# RF.net
KiCad netlist of a schematic drawn in Altium Designer
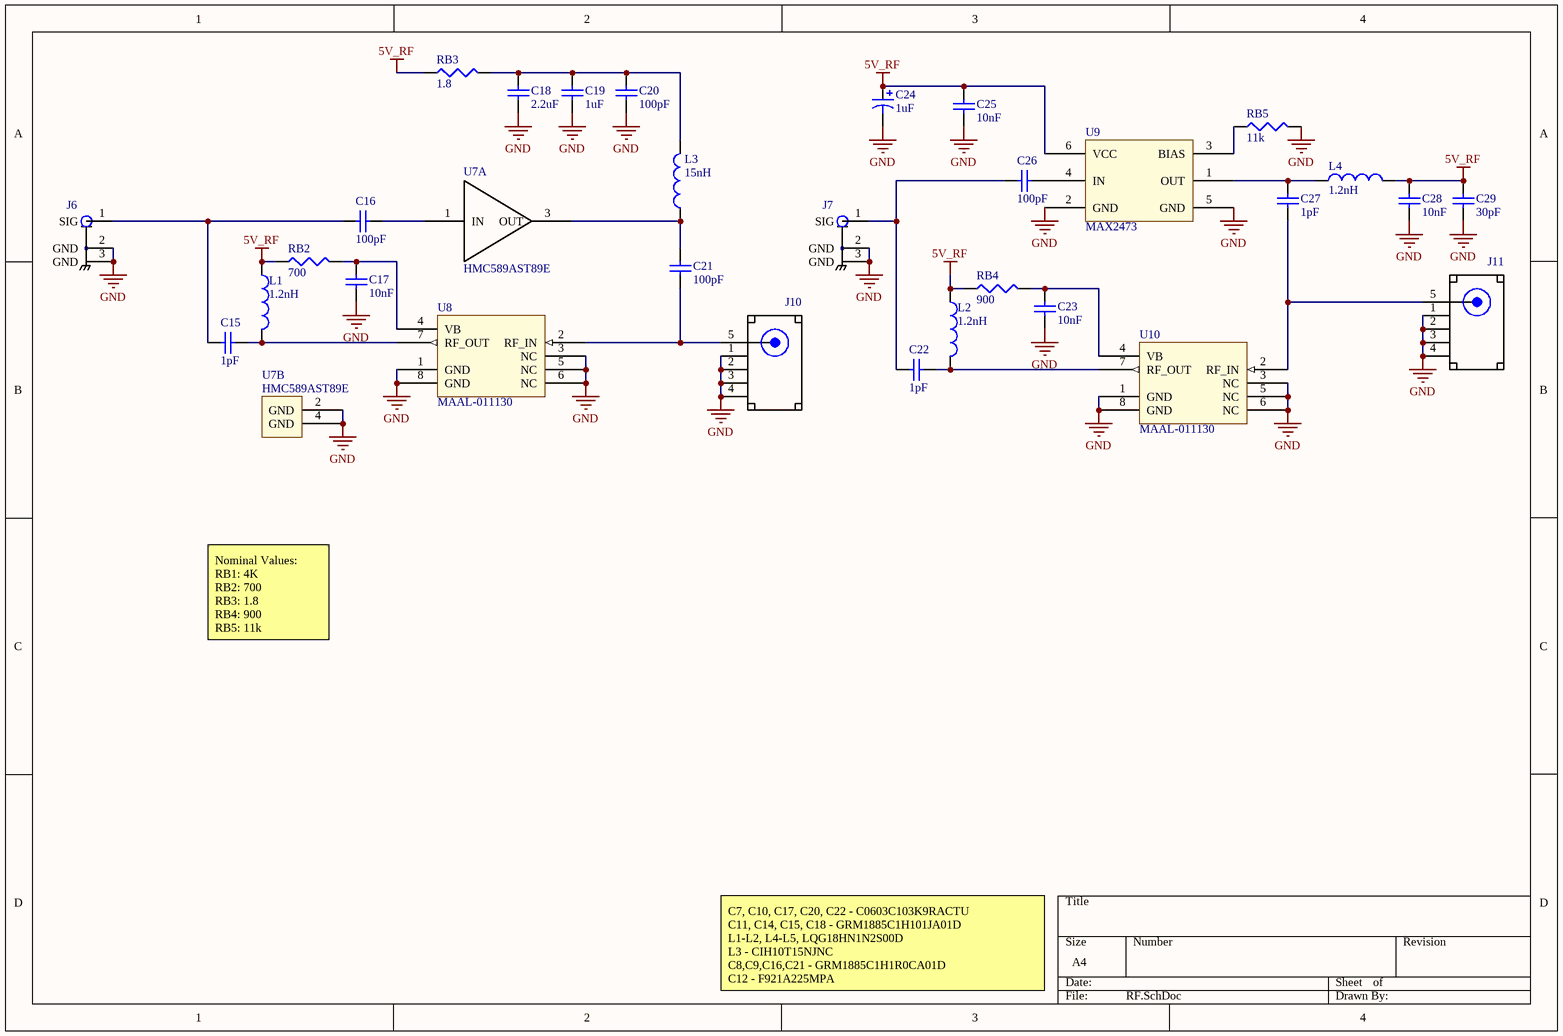
[diagram p0: RF.SchDoc]

(export (version "E")
  (design (tool "Eeschema 10.0.6"))
  (components
    (comp (ref "C15")
      (value "1pF")
      (footprint "CAPC1608X90X35LL10T15")
      (fields (field (name "MANUFACTURER") "Murata") (field (name "PART NUMBER") "GRM1885C1H1R0CA01D"))
      (libsource (lib "Altium Content Vault") (part "CAP"))
    )
    (comp (ref "C16")
      (value "100pF")
      (footprint "CAPC0603(1608)100_N")
      (description "CAP 100pF 50V ±5% 0603 (1608 Metric) Thickness 1mm SMD")
      (fields (field (name "TOLERANCE") "Â±5%"))
      (libsource (lib "Altium Content Vault") (part "CAP"))
    )
    (comp (ref "C17")
      (value "10nF")
      (footprint "CAPC0603(1608)100_L")
      (description "CAP 10nF 6.3V ±10% 0603 (1608 Metric) Thickness 1mm SMD")
      (fields (field (name "TOLERANCE") "Â±10%"))
      (libsource (lib "Altium Content Vault") (part "CAP"))
    )
    (comp (ref "C18")
      (value "2.2uF")
      (footprint "C1206")
      (description "Capacitor (Semiconductor SIM Model)")
      (fields (field (name "MANUFACTURER") "AVX") (field (name "PART NUMBER") "F921A225MPA"))
      (libsource (lib "Miscellaneous Devices") (part "Cap Semi"))
    )
    (comp (ref "C19")
      (value "1uF")
      (footprint "CAPC0603(1608)100_N")
      (description "CAP 100pF 50V ±5% 0603 (1608 Metric) Thickness 1mm SMD")
      (fields (field (name "TOLERANCE") "Â±5%"))
      (libsource (lib "Altium Content Vault") (part "CAP"))
    )
    (comp (ref "C20")
      (value "100pF")
      (footprint "CAPC0603(1608)100_N")
      (description "CAP 100pF 50V ±5% 0603 (1608 Metric) Thickness 1mm SMD")
      (fields (field (name "TOLERANCE") "Â±5%"))
      (libsource (lib "Altium Content Vault") (part "CAP"))
    )
    (comp (ref "C21")
      (value "100pF")
      (footprint "CAPC0603(1608)100_N")
      (description "CAP 100pF 50V ±5% 0603 (1608 Metric) Thickness 1mm SMD")
      (fields (field (name "TOLERANCE") "Â±5%"))
      (libsource (lib "Altium Content Vault") (part "CAP"))
    )
    (comp (ref "C22")
      (value "1pF")
      (footprint "CAPC1608X90X35LL10T15")
      (fields (field (name "MANUFACTURER") "Murata") (field (name "PART NUMBER") "GRM1885C1H1R0CA01D"))
      (libsource (lib "Altium Content Vault") (part "CAP"))
    )
    (comp (ref "C23")
      (value "10nF")
      (footprint "CAPC0603(1608)100_L")
      (description "CAP 10nF 6.3V ±10% 0603 (1608 Metric) Thickness 1mm SMD")
      (fields (field (name "TOLERANCE") "Â±10%"))
      (libsource (lib "Altium Content Vault") (part "CAP"))
    )
    (comp (ref "C24")
      (value "1uF")
      (footprint "CAPAE430X550N")
      (description "Polarized Capacitor (Surface Mount)")
      (fields (field (name "MANUFACTURER") "Panasonic") (field (name "PART NUMBER") "EEE-FC1H1R0R"))
      (libsource (lib "Miscellaneous Devices") (part "Cap Pol3"))
    )
    (comp (ref "C25")
      (value "10nF")
      (footprint "CAPC0603(1608)100_L")
      (description "CAP 10nF 6.3V ±10% 0603 (1608 Metric) Thickness 1mm SMD")
      (fields (field (name "TOLERANCE") "Â±10%"))
      (libsource (lib "Altium Content Vault") (part "CAP"))
    )
    (comp (ref "C26")
      (value "100pF")
      (footprint "CAPC0603(1608)100_N")
      (description "CAP 100pF 50V ±5% 0603 (1608 Metric) Thickness 1mm SMD")
      (fields (field (name "TOLERANCE") "Â±5%"))
      (libsource (lib "Altium Content Vault") (part "CAP"))
    )
    (comp (ref "C27")
      (value "1pF")
      (footprint "CAPC1608X90X35LL10T15")
      (fields (field (name "MANUFACTURER") "Murata") (field (name "PART NUMBER") "GRM1885C1H1R0CA01D"))
      (libsource (lib "Altium Content Vault") (part "CAP"))
    )
    (comp (ref "C28")
      (value "10nF")
      (footprint "CAPC0603(1608)100_L")
      (description "CAP 10nF 6.3V ±10% 0603 (1608 Metric) Thickness 1mm SMD")
      (fields (field (name "TOLERANCE") "Â±10%"))
      (libsource (lib "Altium Content Vault") (part "CAP"))
    )
    (comp (ref "C29")
      (value "30pF")
      (footprint "CAPC1608X90X35LL15T15")
      (fields
        (field (name "MANUFACTURER") "AVX Interconnect / Elco")
        (field (name "PART NUMBER") "06035A300JAT2A")
      )
      (libsource (lib "Altium Content Vault") (part "CAP"))
    )
    (comp (ref "J6")
      (value "1909763-1")
      (footprint "TE_1909763-1")
      (description "CONN UMCC JACK STR 50OHM SMD")
      (fields (field (name "MF") "TE Connectivity"))
      (libsource (lib "Vocore2Parts") (part "1909763-1"))
    )
    (comp (ref "J7")
      (value "1909763-1")
      (footprint "TE_1909763-1")
      (description "CONN UMCC JACK STR 50OHM SMD")
      (fields (field (name "MF") "TE Connectivity"))
      (libsource (lib "Vocore2Parts") (part "1909763-1"))
    )
    (comp (ref "J10")
      (value "5-1814400-1")
      (footprint "CONN_5-1814400-1")
      (description "SMA R/A PCB Skt GZD")
      (fields (field (name "DIGI-KEY_PART_NUMBER") "A97593-ND") (field (name "MF") "TE Connectivity"))
      (libsource (lib "Vocore2Parts") (part "5-1814400-1"))
    )
    (comp (ref "J11")
      (value "5-1814400-1")
      (footprint "CONN_5-1814400-1")
      (description "SMA R/A PCB Skt GZD")
      (fields (field (name "DIGI-KEY_PART_NUMBER") "A97593-ND") (field (name "MF") "TE Connectivity"))
      (libsource (lib "Vocore2Parts") (part "5-1814400-1"))
    )
    (comp (ref "L1")
      (value "1.2nH")
      (footprint "INDC1608L")
      (description "Inductor")
      (fields (field (name "PART NUMBER") "LQG15WH1N2S02D") (field (name "MANUFACTURER") "Murata"))
      (libsource (lib "Miscellaneous Devices") (part "Inductor"))
    )
    (comp (ref "L2")
      (value "1.2nH")
      (footprint "INDC1608L")
      (description "Inductor")
      (fields (field (name "PART NUMBER") "LQG15WH1N2S02D") (field (name "MANUFACTURER") "Murata"))
      (libsource (lib "Miscellaneous Devices") (part "Inductor"))
    )
    (comp (ref "L3")
      (value "15nH")
      (footprint "INDC1608L")
      (description "Inductor")
      (fields (field (name "PART NUMBER") "CIH10T15NJNC") (field (name "MANUFACTURER") "Samsung"))
      (libsource (lib "Miscellaneous Devices") (part "Inductor"))
    )
    (comp (ref "L4")
      (value "1.2nH")
      (footprint "INDC1608L")
      (description "Inductor")
      (fields (field (name "PART NUMBER") "LQG15WH1N2S02D") (field (name "MANUFACTURER") "Murata"))
      (libsource (lib "Miscellaneous Devices") (part "Inductor"))
    )
    (comp (ref "RB2")
      (value "700")
      (footprint "J1-0603")
      (description "Resistor")
      (fields (field (name "PUBLISHER") "Altium Limited"))
      (libsource (lib "Miscellaneous Devices") (part "Res3"))
    )
    (comp (ref "RB3")
      (value "1.8")
      (footprint "J1-0603")
      (description "Resistor")
      (fields (field (name "PUBLISHER") "Altium Limited"))
      (libsource (lib "Miscellaneous Devices") (part "Res3"))
    )
    (comp (ref "RB4")
      (value "900")
      (footprint "C1206")
      (description "Resistor")
      (fields (field (name "PUBLISHER") "Altium Limited"))
      (libsource (lib "Miscellaneous Devices") (part "Res3"))
    )
    (comp (ref "RB5")
      (value "11k")
      (footprint "J1-0603")
      (description "Resistor")
      (fields (field (name "PUBLISHER") "Altium Limited"))
      (libsource (lib "Miscellaneous Devices") (part "Res3"))
    )
    (comp (ref "U7")
      (value "HMC589AST89E")
      (footprint "SOT150P410X160-3N")
      (libsource (lib "Vocore2Parts") (part "HMC589AST89E"))
    )
    (comp (ref "U8")
      (value "MAAL-011130")
      (footprint "PQFN50P200X200X100_HS-9N")
      (libsource (lib "Vocore2Parts") (part "MAAL-011130"))
    )
    (comp (ref "U9")
      (value "MAX2473")
      (footprint "SOT95P280X145-6N")
      (libsource (lib "Vocore2Parts") (part "MAX2473"))
    )
    (comp (ref "U10")
      (value "MAAL-011130")
      (footprint "PQFN50P200X200X100_HS-9N")
      (libsource (lib "Vocore2Parts") (part "MAAL-011130"))
    )
  )
  (nets
    (net (code "1") (name "5V_RF") (class "Default")
      (node (ref "C24") (pin "1") (pinfunction "1_1") (pintype "passive"))
      (node (ref "C25") (pin "2") (pinfunction "2_2") (pintype "passive"))
      (node (ref "C28") (pin "2") (pinfunction "2_2") (pintype "passive"))
      (node (ref "C29") (pin "2") (pinfunction "2_2") (pintype "passive"))
      (node (ref "L1") (pin "2") (pinfunction "2_2") (pintype "passive"))
      (node (ref "L2") (pin "2") (pinfunction "2_2") (pintype "passive"))
      (node (ref "L4") (pin "1") (pinfunction "1_1") (pintype "passive"))
      (node (ref "RB2") (pin "2") (pinfunction "2_2") (pintype "passive"))
      (node (ref "RB3") (pin "2") (pinfunction "2_2") (pintype "passive"))
      (node (ref "RB4") (pin "2") (pinfunction "2_2") (pintype "passive"))
      (node (ref "U9") (pin "6") (pinfunction "VCC_6") (pintype "passive"))
    )
    (net (code "2") (name "GND") (class "Default")
      (node (ref "C17") (pin "1") (pinfunction "1_1") (pintype "passive"))
      (node (ref "C18") (pin "1") (pinfunction "1_1") (pintype "passive"))
      (node (ref "C19") (pin "2") (pinfunction "2_2") (pintype "passive"))
      (node (ref "C20") (pin "2") (pinfunction "2_2") (pintype "passive"))
      (node (ref "C23") (pin "1") (pinfunction "1_1") (pintype "passive"))
      (node (ref "C24") (pin "2") (pinfunction "2_2") (pintype "passive"))
      (node (ref "C25") (pin "1") (pinfunction "1_1") (pintype "passive"))
      (node (ref "C28") (pin "1") (pinfunction "1_1") (pintype "passive"))
      (node (ref "C29") (pin "1") (pinfunction "1_1") (pintype "passive"))
      (node (ref "J10") (pin "1") (pinfunction "GND_1") (pintype "power_in"))
      (node (ref "J10") (pin "2") (pinfunction "GND_2") (pintype "power_in"))
      (node (ref "J10") (pin "3") (pinfunction "GND_3") (pintype "power_in"))
      (node (ref "J10") (pin "4") (pinfunction "GND_4") (pintype "power_in"))
      (node (ref "J11") (pin "1") (pinfunction "GND_1") (pintype "power_in"))
      (node (ref "J11") (pin "2") (pinfunction "GND_2") (pintype "power_in"))
      (node (ref "J11") (pin "3") (pinfunction "GND_3") (pintype "power_in"))
      (node (ref "J11") (pin "4") (pinfunction "GND_4") (pintype "power_in"))
      (node (ref "J6") (pin "2") (pinfunction "GND_2") (pintype "passive"))
      (node (ref "J6") (pin "3") (pinfunction "GND_3") (pintype "passive"))
      (node (ref "J7") (pin "2") (pinfunction "GND_2") (pintype "passive"))
      (node (ref "J7") (pin "3") (pinfunction "GND_3") (pintype "passive"))
      (node (ref "RB5") (pin "1") (pinfunction "1_1") (pintype "passive"))
      (node (ref "U10") (pin "1") (pinfunction "GND_1") (pintype "power_in"))
      (node (ref "U10") (pin "3") (pinfunction "NC_3") (pintype "passive"))
      (node (ref "U10") (pin "5") (pinfunction "NC_5") (pintype "passive"))
      (node (ref "U10") (pin "6") (pinfunction "NC_6") (pintype "passive"))
      (node (ref "U10") (pin "8") (pinfunction "GND_8") (pintype "power_in"))
      (node (ref "U7") (pin "2") (pinfunction "GND_2") (pintype "passive"))
      (node (ref "U7") (pin "4") (pinfunction "GND_4") (pintype "passive"))
      (node (ref "U8") (pin "1") (pinfunction "GND_1") (pintype "power_in"))
      (node (ref "U8") (pin "3") (pinfunction "NC_3") (pintype "passive"))
      (node (ref "U8") (pin "5") (pinfunction "NC_5") (pintype "passive"))
      (node (ref "U8") (pin "6") (pinfunction "NC_6") (pintype "passive"))
      (node (ref "U8") (pin "8") (pinfunction "GND_8") (pintype "power_in"))
      (node (ref "U9") (pin "2") (pinfunction "GND_2") (pintype "power_in"))
      (node (ref "U9") (pin "5") (pinfunction "GND_5") (pintype "passive"))
    )
    (net (code "3") (name "Net-(C18-Pad2)") (class "Default")
      (node (ref "C18") (pin "2") (pinfunction "2_2") (pintype "passive"))
      (node (ref "C19") (pin "1") (pinfunction "1_1") (pintype "passive"))
      (node (ref "C20") (pin "1") (pinfunction "1_1") (pintype "passive"))
      (node (ref "L3") (pin "1") (pinfunction "1_1") (pintype "passive"))
      (node (ref "RB3") (pin "1") (pinfunction "1_1") (pintype "passive"))
    )
    (net (code "4") (name "Net-(J6-SIG)") (class "Default")
      (node (ref "C15") (pin "1") (pinfunction "1_1") (pintype "passive"))
      (node (ref "C16") (pin "1") (pinfunction "1_1") (pintype "passive"))
      (node (ref "J6") (pin "1") (pinfunction "SIG_1") (pintype "passive"))
    )
    (net (code "5") (name "Net-(J7-SIG)") (class "Default")
      (node (ref "C22") (pin "1") (pinfunction "1_1") (pintype "passive"))
      (node (ref "C26") (pin "1") (pinfunction "1_1") (pintype "passive"))
      (node (ref "J7") (pin "1") (pinfunction "SIG_1") (pintype "passive"))
    )
    (net (code "6") (name "Net-(J10-SIGNAL)") (class "Default")
      (node (ref "C21") (pin "2") (pinfunction "2_2") (pintype "passive"))
      (node (ref "J10") (pin "5") (pinfunction "SIGNAL_5") (pintype "passive"))
      (node (ref "U8") (pin "2") (pinfunction "RF_IN_2") (pintype "input"))
    )
    (net (code "7") (name "Net-(J11-SIGNAL)") (class "Default")
      (node (ref "C27") (pin "1") (pinfunction "1_1") (pintype "passive"))
      (node (ref "J11") (pin "5") (pinfunction "SIGNAL_5") (pintype "passive"))
      (node (ref "U10") (pin "2") (pinfunction "RF_IN_2") (pintype "input"))
    )
    (net (code "8") (name "Net-(U7A-IN)") (class "Default")
      (node (ref "C16") (pin "2") (pinfunction "2_2") (pintype "passive"))
      (node (ref "U7") (pin "1") (pinfunction "IN_1") (pintype "passive"))
    )
    (net (code "9") (name "Net-(U7A-OUT)") (class "Default")
      (node (ref "C21") (pin "1") (pinfunction "1_1") (pintype "passive"))
      (node (ref "L3") (pin "2") (pinfunction "2_2") (pintype "passive"))
      (node (ref "U7") (pin "3") (pinfunction "OUT_3") (pintype "passive"))
    )
    (net (code "10") (name "Net-(U8-RF_OUT)") (class "Default")
      (node (ref "C15") (pin "2") (pinfunction "2_2") (pintype "passive"))
      (node (ref "L1") (pin "1") (pinfunction "1_1") (pintype "passive"))
      (node (ref "U8") (pin "7") (pinfunction "RF_OUT_7") (pintype "output"))
    )
    (net (code "11") (name "Net-(U8-VB)") (class "Default")
      (node (ref "C17") (pin "2") (pinfunction "2_2") (pintype "passive"))
      (node (ref "RB2") (pin "1") (pinfunction "1_1") (pintype "passive"))
      (node (ref "U8") (pin "4") (pinfunction "VB_4") (pintype "passive"))
    )
    (net (code "12") (name "Net-(U9-BIAS)") (class "Default")
      (node (ref "RB5") (pin "2") (pinfunction "2_2") (pintype "passive"))
      (node (ref "U9") (pin "3") (pinfunction "BIAS_3") (pintype "passive"))
    )
    (net (code "13") (name "Net-(U9-IN)") (class "Default")
      (node (ref "C26") (pin "2") (pinfunction "2_2") (pintype "passive"))
      (node (ref "U9") (pin "4") (pinfunction "IN_4") (pintype "passive"))
    )
    (net (code "14") (name "Net-(U9-OUT)") (class "Default")
      (node (ref "C27") (pin "2") (pinfunction "2_2") (pintype "passive"))
      (node (ref "L4") (pin "2") (pinfunction "2_2") (pintype "passive"))
      (node (ref "U9") (pin "1") (pinfunction "OUT_1") (pintype "passive"))
    )
    (net (code "15") (name "Net-(U10-RF_OUT)") (class "Default")
      (node (ref "C22") (pin "2") (pinfunction "2_2") (pintype "passive"))
      (node (ref "L2") (pin "1") (pinfunction "1_1") (pintype "passive"))
      (node (ref "U10") (pin "7") (pinfunction "RF_OUT_7") (pintype "output"))
    )
    (net (code "16") (name "Net-(U10-VB)") (class "Default")
      (node (ref "C23") (pin "2") (pinfunction "2_2") (pintype "passive"))
      (node (ref "RB4") (pin "1") (pinfunction "1_1") (pintype "passive"))
      (node (ref "U10") (pin "4") (pinfunction "VB_4") (pintype "passive"))
    )
  )
)
